# DDMTD.net
KiCad netlist of a schematic drawn in Altium Designer
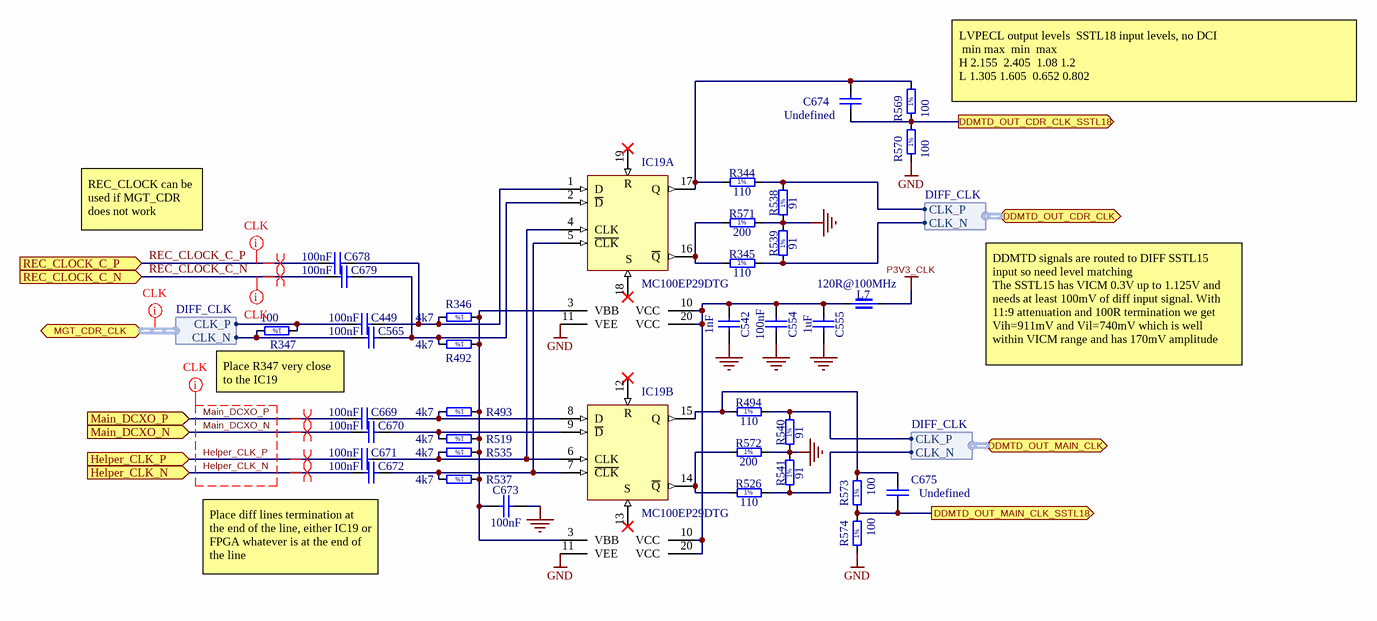
[diagram p0: DDMTD.SchDoc]

(export (version "E")
  (design (tool "Eeschema 10.0.6"))
  (components
    (comp (ref "C449")
      (value "100nF")
      (footprint "CAPC1005X55N")
      (description "Non-polarised capacitor")
      (fields
        (field (name "MANUFACTURER PART NUMBER") "CC0402_100NF_16V_10%_X5R")
        (field (name "MANUFACTURER") "GENERIC")
        (field (name "AUTHOR") "CERN DEM JLC")
      )
      (libsource (lib "Capacitors") (part "Capacitor - non polarized"))
    )
    (comp (ref "C542")
      (value "1nF")
      (footprint "CAPC0603X33N")
      (description "Non-polarised capacitor")
      (fields
        (field (name "MANUFACTURER PART NUMBER") "CC0201_1NF_16V_10%_X5R")
        (field (name "MANUFACTURER") "GENERIC")
        (field (name "AUTHOR") "CERN DEM JLC")
      )
      (libsource (lib "Capacitors") (part "Capacitor - non polarized"))
    )
    (comp (ref "C554")
      (value "100nF")
      (footprint "CAPC0603X33N")
      (description "Non-polarised capacitor")
      (fields
        (field (name "MANUFACTURER PART NUMBER") "CC0201_100NF_6.3V_10%_X5R")
        (field (name "MANUFACTURER") "GENERIC")
        (field (name "AUTHOR") "CERN DEM JLC")
      )
      (libsource (lib "Capacitors") (part "Capacitor - non polarized"))
    )
    (comp (ref "C555")
      (value "1uF")
      (footprint "CAPC1005X55N")
      (description "Non-polarised capacitor")
      (fields
        (field (name "MANUFACTURER PART NUMBER") "CC0402_1UF_16V_10%_X5R")
        (field (name "MANUFACTURER") "GENERIC")
        (field (name "AUTHOR") "CERN DEM JLC")
      )
      (libsource (lib "Capacitors") (part "Capacitor - non polarized"))
    )
    (comp (ref "C565")
      (value "100nF")
      (footprint "CAPC1005X55N")
      (description "Non-polarised capacitor")
      (fields
        (field (name "MANUFACTURER PART NUMBER") "CC0402_100NF_16V_10%_X5R")
        (field (name "MANUFACTURER") "GENERIC")
        (field (name "AUTHOR") "CERN DEM JLC")
      )
      (libsource (lib "Capacitors") (part "Capacitor - non polarized"))
    )
    (comp (ref "C669")
      (value "100nF")
      (footprint "CAPC1005X55N")
      (description "Non-polarised capacitor")
      (fields
        (field (name "MANUFACTURER PART NUMBER") "CC0402_100NF_16V_10%_X5R")
        (field (name "MANUFACTURER") "GENERIC")
        (field (name "AUTHOR") "CERN DEM JLC")
      )
      (libsource (lib "Capacitors") (part "Capacitor - non polarized"))
    )
    (comp (ref "C670")
      (value "100nF")
      (footprint "CAPC1005X55N")
      (description "Non-polarised capacitor")
      (fields
        (field (name "MANUFACTURER PART NUMBER") "CC0402_100NF_16V_10%_X5R")
        (field (name "MANUFACTURER") "GENERIC")
        (field (name "AUTHOR") "CERN DEM JLC")
      )
      (libsource (lib "Capacitors") (part "Capacitor - non polarized"))
    )
    (comp (ref "C671")
      (value "100nF")
      (footprint "CAPC1005X55N")
      (description "Non-polarised capacitor")
      (fields
        (field (name "MANUFACTURER PART NUMBER") "CC0402_100NF_16V_10%_X5R")
        (field (name "MANUFACTURER") "GENERIC")
        (field (name "AUTHOR") "CERN DEM JLC")
      )
      (libsource (lib "Capacitors") (part "Capacitor - non polarized"))
    )
    (comp (ref "C672")
      (value "100nF")
      (footprint "CAPC1005X55N")
      (description "Non-polarised capacitor")
      (fields
        (field (name "MANUFACTURER PART NUMBER") "CC0402_100NF_16V_10%_X5R")
        (field (name "MANUFACTURER") "GENERIC")
        (field (name "AUTHOR") "CERN DEM JLC")
      )
      (libsource (lib "Capacitors") (part "Capacitor - non polarized"))
    )
    (comp (ref "C673")
      (value "100nF")
      (footprint "CAPC0603X33N")
      (description "Non-polarised capacitor")
      (fields
        (field (name "MANUFACTURER PART NUMBER") "CC0201_100NF_6.3V_10%_X5R")
        (field (name "MANUFACTURER") "GENERIC")
        (field (name "AUTHOR") "CERN DEM JLC")
      )
      (libsource (lib "Capacitors") (part "Capacitor - non polarized"))
    )
    (comp (ref "C674")
      (value "Undefined")
      (footprint "CAPC1005X55N")
      (description "Non-polarised capacitor")
      (fields (field (name "PART NUMBER") "CC0402_NO-VALUE") (field (name "AUTHOR") "CERN DEM JLC"))
      (libsource (lib "Capacitors") (part "Capacitor - non polarized"))
    )
    (comp (ref "C675")
      (value "Undefined")
      (footprint "CAPC1005X55N")
      (description "Non-polarised capacitor")
      (fields (field (name "PART NUMBER") "CC0402_NO-VALUE") (field (name "AUTHOR") "CERN DEM JLC"))
      (libsource (lib "Capacitors") (part "Capacitor - non polarized"))
    )
    (comp (ref "C678")
      (value "100nF")
      (footprint "CAPC1005X55N")
      (description "Non-polarised capacitor")
      (fields
        (field (name "MANUFACTURER PART NUMBER") "CC0402_100NF_16V_10%_X5R")
        (field (name "MANUFACTURER") "GENERIC")
        (field (name "AUTHOR") "CERN DEM JLC")
      )
      (libsource (lib "Capacitors") (part "Capacitor - non polarized"))
    )
    (comp (ref "C679")
      (value "100nF")
      (footprint "CAPC1005X55N")
      (description "Non-polarised capacitor")
      (fields
        (field (name "MANUFACTURER PART NUMBER") "CC0402_100NF_16V_10%_X5R")
        (field (name "MANUFACTURER") "GENERIC")
        (field (name "AUTHOR") "CERN DEM JLC")
      )
      (libsource (lib "Capacitors") (part "Capacitor - non polarized"))
    )
    (comp (ref "IC19")
      (value "MC100EP29DTG")
      (footprint "SOP65P640X120-20N")
      (description "3.3V/5V ECL Dual Differential Data and Clock D Flip-Flop With Set and Reset")
      (fields (field (name "MANUFACTURER") "ON SEMICONDUCTOR") (field (name "AUTHOR") "CERN DEM JLC"))
      (libsource (lib "ICs And Semiconductors") (part "100EP29D"))
    )
    (comp (ref "L7")
      (value "120R@100MHz")
      (footprint "INDC1608X95N")
      (fields
        (field (name "MANUFACTURER PART NUMBER") "BLM18PG121SN1D")
        (field (name "MANUFACTURER") "MURATA")
        (field (name "PART NUMBER") "IND0603_MURATA_BLM18PG121SN1D")
        (field (name "AUTHOR") "CERN DEM BC")
      )
      (libsource (lib "Inductors & Transformers") (part "Ferrite Bead"))
    )
    (comp (ref "R344")
      (value "110")
      (footprint "RESC1005X40N")
      (description "Resistor - 1%")
      (fields
        (field (name "MANUFACTURER PART NUMBER") "R0402_110R_1%_0.0625W_100PPM")
        (field (name "MANUFACTURER") "GENERIC")
        (field (name "AUTHOR") "CERN DEM JLC")
      )
      (libsource (lib "Resistors") (part "Resistor - 1%"))
    )
    (comp (ref "R345")
      (value "110")
      (footprint "RESC1005X40N")
      (description "Resistor - 1%")
      (fields
        (field (name "MANUFACTURER PART NUMBER") "R0402_110R_1%_0.0625W_100PPM")
        (field (name "MANUFACTURER") "GENERIC")
        (field (name "AUTHOR") "CERN DEM JLC")
      )
      (libsource (lib "Resistors") (part "Resistor - 1%"))
    )
    (comp (ref "R346")
      (value "4k7")
      (footprint "RESC1005X40N")
      (description "Resistor - 1%")
      (fields
        (field (name "MANUFACTURER PART NUMBER") "R0402_4K7_1%_0.0625W_100PPM")
        (field (name "MANUFACTURER") "GENERIC")
        (field (name "AUTHOR") "CERN DEM JLC")
      )
      (libsource (lib "Resistors") (part "Resistor - 1%"))
    )
    (comp (ref "R347")
      (value "100")
      (footprint "RESC1005X40N")
      (description "Resistor - 1%")
      (fields
        (field (name "MANUFACTURER PART NUMBER") "R0402_100R_1%_0.0625W_100PPM")
        (field (name "MANUFACTURER") "GENERIC")
        (field (name "AUTHOR") "CERN DEM JLC")
      )
      (libsource (lib "Resistors") (part "Resistor - 1%"))
    )
    (comp (ref "R492")
      (value "4k7")
      (footprint "RESC1005X40N")
      (description "Resistor - 1%")
      (fields
        (field (name "MANUFACTURER PART NUMBER") "R0402_4K7_1%_0.0625W_100PPM")
        (field (name "MANUFACTURER") "GENERIC")
        (field (name "AUTHOR") "CERN DEM JLC")
      )
      (libsource (lib "Resistors") (part "Resistor - 1%"))
    )
    (comp (ref "R493")
      (value "4k7")
      (footprint "RESC1005X40N")
      (description "Resistor - 1%")
      (fields
        (field (name "MANUFACTURER PART NUMBER") "R0402_4K7_1%_0.0625W_100PPM")
        (field (name "MANUFACTURER") "GENERIC")
        (field (name "AUTHOR") "CERN DEM JLC")
      )
      (libsource (lib "Resistors") (part "Resistor - 1%"))
    )
    (comp (ref "R494")
      (value "110")
      (footprint "RESC1005X40N")
      (description "Resistor - 1%")
      (fields
        (field (name "MANUFACTURER PART NUMBER") "R0402_110R_1%_0.0625W_100PPM")
        (field (name "MANUFACTURER") "GENERIC")
        (field (name "AUTHOR") "CERN DEM JLC")
      )
      (libsource (lib "Resistors") (part "Resistor - 1%"))
    )
    (comp (ref "R519")
      (value "4k7")
      (footprint "RESC1005X40N")
      (description "Resistor - 1%")
      (fields
        (field (name "MANUFACTURER PART NUMBER") "R0402_4K7_1%_0.0625W_100PPM")
        (field (name "MANUFACTURER") "GENERIC")
        (field (name "AUTHOR") "CERN DEM JLC")
      )
      (libsource (lib "Resistors") (part "Resistor - 1%"))
    )
    (comp (ref "R526")
      (value "110")
      (footprint "RESC1005X40N")
      (description "Resistor - 1%")
      (fields
        (field (name "MANUFACTURER PART NUMBER") "R0402_110R_1%_0.0625W_100PPM")
        (field (name "MANUFACTURER") "GENERIC")
        (field (name "AUTHOR") "CERN DEM JLC")
      )
      (libsource (lib "Resistors") (part "Resistor - 1%"))
    )
    (comp (ref "R535")
      (value "4k7")
      (footprint "RESC1005X40N")
      (description "Resistor - 1%")
      (fields
        (field (name "MANUFACTURER PART NUMBER") "R0402_4K7_1%_0.0625W_100PPM")
        (field (name "MANUFACTURER") "GENERIC")
        (field (name "AUTHOR") "CERN DEM JLC")
      )
      (libsource (lib "Resistors") (part "Resistor - 1%"))
    )
    (comp (ref "R537")
      (value "4k7")
      (footprint "RESC1005X40N")
      (description "Resistor - 1%")
      (fields
        (field (name "MANUFACTURER PART NUMBER") "R0402_4K7_1%_0.0625W_100PPM")
        (field (name "MANUFACTURER") "GENERIC")
        (field (name "AUTHOR") "CERN DEM JLC")
      )
      (libsource (lib "Resistors") (part "Resistor - 1%"))
    )
    (comp (ref "R538")
      (value "91")
      (footprint "RESC1005X40N")
      (description "Resistor - 1%")
      (fields
        (field (name "MANUFACTURER PART NUMBER") "R0402_91R_1%_0.0625W_100PPM")
        (field (name "MANUFACTURER") "GENERIC")
        (field (name "AUTHOR") "CERN DEM JLC")
      )
      (libsource (lib "Resistors") (part "Resistor - 1%"))
    )
    (comp (ref "R539")
      (value "91")
      (footprint "RESC1005X40N")
      (description "Resistor - 1%")
      (fields
        (field (name "MANUFACTURER PART NUMBER") "R0402_91R_1%_0.0625W_100PPM")
        (field (name "MANUFACTURER") "GENERIC")
        (field (name "AUTHOR") "CERN DEM JLC")
      )
      (libsource (lib "Resistors") (part "Resistor - 1%"))
    )
    (comp (ref "R540")
      (value "91")
      (footprint "RESC1005X40N")
      (description "Resistor - 1%")
      (fields
        (field (name "MANUFACTURER PART NUMBER") "R0402_91R_1%_0.0625W_100PPM")
        (field (name "MANUFACTURER") "GENERIC")
        (field (name "AUTHOR") "CERN DEM JLC")
      )
      (libsource (lib "Resistors") (part "Resistor - 1%"))
    )
    (comp (ref "R541")
      (value "91")
      (footprint "RESC1005X40N")
      (description "Resistor - 1%")
      (fields
        (field (name "MANUFACTURER PART NUMBER") "R0402_91R_1%_0.0625W_100PPM")
        (field (name "MANUFACTURER") "GENERIC")
        (field (name "AUTHOR") "CERN DEM JLC")
      )
      (libsource (lib "Resistors") (part "Resistor - 1%"))
    )
    (comp (ref "R569")
      (value "100")
      (footprint "RESC1005X40N")
      (description "Resistor - 1%")
      (fields
        (field (name "MANUFACTURER PART NUMBER") "R0402_100R_1%_0.0625W_100PPM")
        (field (name "MANUFACTURER") "GENERIC")
        (field (name "AUTHOR") "CERN DEM JLC")
      )
      (libsource (lib "Resistors") (part "Resistor - 1%"))
    )
    (comp (ref "R570")
      (value "100")
      (footprint "RESC1005X40N")
      (description "Resistor - 1%")
      (fields
        (field (name "MANUFACTURER PART NUMBER") "R0402_100R_1%_0.0625W_100PPM")
        (field (name "MANUFACTURER") "GENERIC")
        (field (name "AUTHOR") "CERN DEM JLC")
      )
      (libsource (lib "Resistors") (part "Resistor - 1%"))
    )
    (comp (ref "R571")
      (value "200")
      (footprint "RESC1005X40N")
      (description "Resistor - 1%")
      (fields
        (field (name "PART NUMBER") "R0402_200R_1%_0.0625W_100PPM")
        (field (name "POWER") "0.0625W")
        (field (name "AUTHOR") "CERN DEM JLC")
      )
      (libsource (lib "Resistors") (part "Resistor - 1%"))
    )
    (comp (ref "R572")
      (value "200")
      (footprint "RESC1005X40N")
      (description "Resistor - 1%")
      (fields
        (field (name "PART NUMBER") "R0402_200R_1%_0.0625W_100PPM")
        (field (name "POWER") "0.0625W")
        (field (name "AUTHOR") "CERN DEM JLC")
      )
      (libsource (lib "Resistors") (part "Resistor - 1%"))
    )
    (comp (ref "R573")
      (value "100")
      (footprint "RESC1005X40N")
      (description "Resistor - 1%")
      (fields
        (field (name "MANUFACTURER PART NUMBER") "R0402_100R_1%_0.0625W_100PPM")
        (field (name "MANUFACTURER") "GENERIC")
        (field (name "AUTHOR") "CERN DEM JLC")
      )
      (libsource (lib "Resistors") (part "Resistor - 1%"))
    )
    (comp (ref "R574")
      (value "100")
      (footprint "RESC1005X40N")
      (description "Resistor - 1%")
      (fields
        (field (name "MANUFACTURER PART NUMBER") "R0402_100R_1%_0.0625W_100PPM")
        (field (name "MANUFACTURER") "GENERIC")
        (field (name "AUTHOR") "CERN DEM JLC")
      )
      (libsource (lib "Resistors") (part "Resistor - 1%"))
    )
  )
  (nets
    (net (code "2") (name "/DDMTD_OUT_CDR_CLK_SSTL18") (class "Default")
      (node (ref "C674") (pin "1") (pinfunction "1_1") (pintype "passive"))
      (node (ref "R569") (pin "1") (pinfunction "1_1") (pintype "passive"))
      (node (ref "R570") (pin "2") (pinfunction "2_2") (pintype "passive"))
    )
    (net (code "3") (name "/DDMTD_OUT_MAIN_CLK_SSTL18") (class "Default")
      (node (ref "C675") (pin "1") (pinfunction "1_1") (pintype "passive"))
      (node (ref "R573") (pin "1") (pinfunction "1_1") (pintype "passive"))
      (node (ref "R574") (pin "2") (pinfunction "2_2") (pintype "passive"))
    )
    (net (code "4") (name "/Helper_CLK_N") (class "Default")
      (node (ref "C672") (pin "1") (pinfunction "1_1") (pintype "passive"))
    )
    (net (code "5") (name "/Helper_CLK_P") (class "Default")
      (node (ref "C671") (pin "1") (pinfunction "1_1") (pintype "passive"))
    )
    (net (code "6") (name "/Main_DCXO_N") (class "Default")
      (node (ref "C670") (pin "1") (pinfunction "1_1") (pintype "passive"))
    )
    (net (code "7") (name "/Main_DCXO_P") (class "Default")
      (node (ref "C669") (pin "1") (pinfunction "1_1") (pintype "passive"))
    )
    (net (code "8") (name "/REC_CLOCK_C_N") (class "Default")
      (node (ref "C679") (pin "1") (pinfunction "1_1") (pintype "passive"))
    )
    (net (code "9") (name "/REC_CLOCK_C_P") (class "Default")
      (node (ref "C678") (pin "1") (pinfunction "1_1") (pintype "passive"))
    )
    (net (code "11") (name "GND") (class "Default")
      (node (ref "C542") (pin "1") (pinfunction "1_1") (pintype "passive"))
      (node (ref "C554") (pin "1") (pinfunction "1_1") (pintype "passive"))
      (node (ref "C555") (pin "2") (pinfunction "2_2") (pintype "passive"))
      (node (ref "C673") (pin "1") (pinfunction "1_1") (pintype "passive"))
      (node (ref "IC19") (pin "11") (pinfunction "VEE_11") (pintype "power_in"))
      (node (ref "R538") (pin "1") (pinfunction "1_1") (pintype "passive"))
      (node (ref "R539") (pin "2") (pinfunction "2_2") (pintype "passive"))
      (node (ref "R540") (pin "1") (pinfunction "1_1") (pintype "passive"))
      (node (ref "R541") (pin "2") (pinfunction "2_2") (pintype "passive"))
      (node (ref "R570") (pin "1") (pinfunction "1_1") (pintype "passive"))
      (node (ref "R571") (pin "2") (pinfunction "2_2") (pintype "passive"))
      (node (ref "R572") (pin "2") (pinfunction "2_2") (pintype "passive"))
      (node (ref "R574") (pin "1") (pinfunction "1_1") (pintype "passive"))
    )
    (net (code "12") (name "Net-(C449-Pad1)") (class "Default")
      (node (ref "C449") (pin "1") (pinfunction "1_1") (pintype "passive"))
      (node (ref "R347") (pin "1") (pinfunction "1_1") (pintype "passive"))
    )
    (net (code "13") (name "Net-(C542-Pad2)") (class "Default")
      (node (ref "C542") (pin "2") (pinfunction "2_2") (pintype "passive"))
      (node (ref "C554") (pin "2") (pinfunction "2_2") (pintype "passive"))
      (node (ref "C555") (pin "1") (pinfunction "1_1") (pintype "passive"))
      (node (ref "IC19") (pin "10") (pinfunction "VCC_10") (pintype "power_in"))
      (node (ref "IC19") (pin "20") (pinfunction "VCC_20") (pintype "power_in"))
      (node (ref "L7") (pin "2") (pinfunction "2_2") (pintype "passive"))
    )
    (net (code "14") (name "Net-(C565-Pad1)") (class "Default")
      (node (ref "C565") (pin "1") (pinfunction "1_1") (pintype "passive"))
      (node (ref "R347") (pin "2") (pinfunction "2_2") (pintype "passive"))
    )
    (net (code "15") (name "Net-(IC19A-CLK)") (class "Default")
      (node (ref "C671") (pin "2") (pinfunction "2_2") (pintype "passive"))
      (node (ref "IC19") (pin "4") (pinfunction "CLK_4") (pintype "input"))
      (node (ref "IC19") (pin "6") (pinfunction "CLK_6") (pintype "input"))
      (node (ref "R535") (pin "2") (pinfunction "2_2") (pintype "passive"))
    )
    (net (code "16") (name "Net-(IC19A-D)") (class "Default")
      (node (ref "C449") (pin "2") (pinfunction "2_2") (pintype "passive"))
      (node (ref "C678") (pin "2") (pinfunction "2_2") (pintype "passive"))
      (node (ref "IC19") (pin "1") (pinfunction "D_1") (pintype "input"))
      (node (ref "R346") (pin "2") (pinfunction "2_2") (pintype "passive"))
    )
    (net (code "17") (name "Net-(IC19A-Q)") (class "Default")
      (node (ref "C674") (pin "2") (pinfunction "2_2") (pintype "passive"))
      (node (ref "IC19") (pin "17") (pinfunction "Q_17") (pintype "output"))
      (node (ref "R344") (pin "1") (pinfunction "1_1") (pintype "passive"))
      (node (ref "R569") (pin "2") (pinfunction "2_2") (pintype "passive"))
    )
    (net (code "18") (name "Net-(IC19A-VBB)") (class "Default")
      (node (ref "C673") (pin "2") (pinfunction "2_2") (pintype "passive"))
      (node (ref "IC19") (pin "3") (pinfunction "VBB_3") (pintype "power_in"))
      (node (ref "R346") (pin "1") (pinfunction "1_1") (pintype "passive"))
      (node (ref "R492") (pin "1") (pinfunction "1_1") (pintype "passive"))
      (node (ref "R493") (pin "1") (pinfunction "1_1") (pintype "passive"))
      (node (ref "R519") (pin "1") (pinfunction "1_1") (pintype "passive"))
      (node (ref "R535") (pin "1") (pinfunction "1_1") (pintype "passive"))
      (node (ref "R537") (pin "1") (pinfunction "1_1") (pintype "passive"))
    )
    (net (code "19") (name "Net-(IC19A-~{CLK})") (class "Default")
      (node (ref "C672") (pin "2") (pinfunction "2_2") (pintype "passive"))
      (node (ref "IC19") (pin "5") (pinfunction "~{CLK}_5") (pintype "input"))
      (node (ref "IC19") (pin "7") (pinfunction "~{CLK}_7") (pintype "input"))
      (node (ref "R537") (pin "2") (pinfunction "2_2") (pintype "passive"))
    )
    (net (code "20") (name "Net-(IC19A-~{D})") (class "Default")
      (node (ref "C565") (pin "2") (pinfunction "2_2") (pintype "passive"))
      (node (ref "C679") (pin "2") (pinfunction "2_2") (pintype "passive"))
      (node (ref "IC19") (pin "2") (pinfunction "~{D}_2") (pintype "input"))
      (node (ref "R492") (pin "2") (pinfunction "2_2") (pintype "passive"))
    )
    (net (code "21") (name "Net-(IC19A-~{Q})") (class "Default")
      (node (ref "IC19") (pin "16") (pinfunction "~{Q}_16") (pintype "output"))
      (node (ref "R345") (pin "1") (pinfunction "1_1") (pintype "passive"))
      (node (ref "R571") (pin "1") (pinfunction "1_1") (pintype "passive"))
    )
    (net (code "22") (name "Net-(IC19B-D)") (class "Default")
      (node (ref "C669") (pin "2") (pinfunction "2_2") (pintype "passive"))
      (node (ref "IC19") (pin "8") (pinfunction "D_8") (pintype "input"))
      (node (ref "R493") (pin "2") (pinfunction "2_2") (pintype "passive"))
    )
    (net (code "23") (name "Net-(IC19B-Q)") (class "Default")
      (node (ref "C675") (pin "2") (pinfunction "2_2") (pintype "passive"))
      (node (ref "IC19") (pin "15") (pinfunction "Q_15") (pintype "output"))
      (node (ref "R494") (pin "1") (pinfunction "1_1") (pintype "passive"))
      (node (ref "R573") (pin "2") (pinfunction "2_2") (pintype "passive"))
    )
    (net (code "24") (name "Net-(IC19B-~{D})") (class "Default")
      (node (ref "C670") (pin "2") (pinfunction "2_2") (pintype "passive"))
      (node (ref "IC19") (pin "9") (pinfunction "~{D}_9") (pintype "input"))
      (node (ref "R519") (pin "2") (pinfunction "2_2") (pintype "passive"))
    )
    (net (code "25") (name "Net-(IC19B-~{Q})") (class "Default")
      (node (ref "IC19") (pin "14") (pinfunction "~{Q}_14") (pintype "output"))
      (node (ref "R526") (pin "1") (pinfunction "1_1") (pintype "passive"))
      (node (ref "R572") (pin "1") (pinfunction "1_1") (pintype "passive"))
    )
    (net (code "26") (name "Net-(R344-Pad2)") (class "Default")
      (node (ref "R344") (pin "2") (pinfunction "2_2") (pintype "passive"))
      (node (ref "R538") (pin "2") (pinfunction "2_2") (pintype "passive"))
    )
    (net (code "27") (name "Net-(R345-Pad2)") (class "Default")
      (node (ref "R345") (pin "2") (pinfunction "2_2") (pintype "passive"))
      (node (ref "R539") (pin "1") (pinfunction "1_1") (pintype "passive"))
    )
    (net (code "28") (name "Net-(R494-Pad2)") (class "Default")
      (node (ref "R494") (pin "2") (pinfunction "2_2") (pintype "passive"))
      (node (ref "R540") (pin "2") (pinfunction "2_2") (pintype "passive"))
    )
    (net (code "29") (name "Net-(R526-Pad2)") (class "Default")
      (node (ref "R526") (pin "2") (pinfunction "2_2") (pintype "passive"))
      (node (ref "R541") (pin "1") (pinfunction "1_1") (pintype "passive"))
    )
    (net (code "30") (name "P3V3_CLK") (class "Default")
      (node (ref "L7") (pin "1") (pinfunction "1_1") (pintype "passive"))
    )
    (net (code "31") (name "unconnected-(IC19A-R-Pad19)") (class "Default")
      (node (ref "IC19") (pin "19") (pinfunction "R_19") (pintype "input+no_connect"))
    )
    (net (code "32") (name "unconnected-(IC19A-S-Pad18)") (class "Default")
      (node (ref "IC19") (pin "18") (pinfunction "S_18") (pintype "input+no_connect"))
    )
    (net (code "33") (name "unconnected-(IC19B-R-Pad12)") (class "Default")
      (node (ref "IC19") (pin "12") (pinfunction "R_12") (pintype "input+no_connect"))
    )
    (net (code "34") (name "unconnected-(IC19B-S-Pad13)") (class "Default")
      (node (ref "IC19") (pin "13") (pinfunction "S_13") (pintype "input+no_connect"))
    )
  )
)
